# komagoma-2.net
KiCad netlist of a schematic drawn in EAGLE
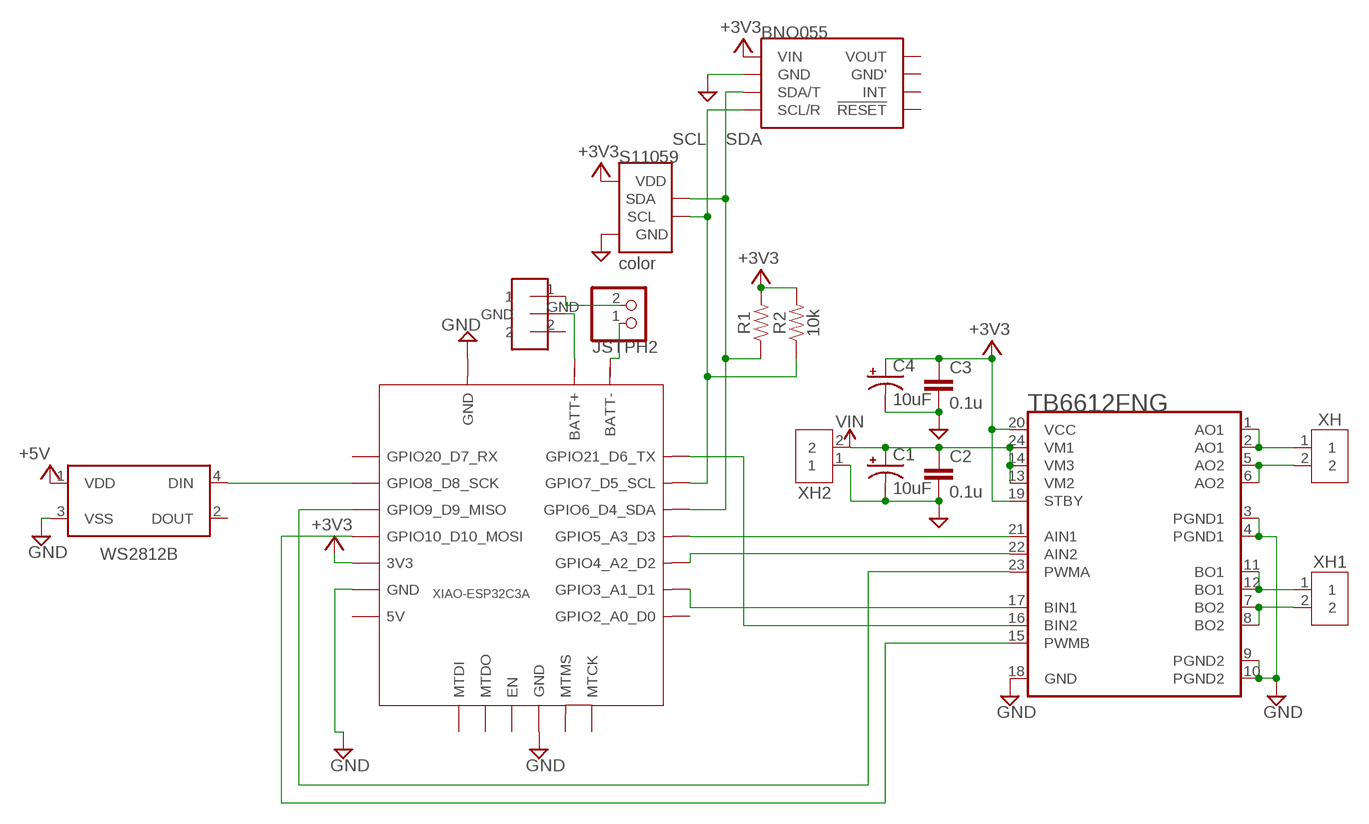
[diagram p0: schematic, sheet 1]

(export (version "E")
  (design (tool "Eeschema 10.0.6"))
  (components
    (comp (ref "C1")
      (value "10uF")
      (footprint "eagle-import:CPOL-RADIAL-2.5MM-5MM-KIT")
      (libsource (lib "eagle-import") (part "10UF-POLAR-RADIAL-2.5MM-KIT-25V-20%"))
    )
    (comp (ref "C2")
      (value "0.1u")
      (footprint "eagle-import:C1608")
      (libsource (lib "eagle-import") (part "C-EUC1608"))
    )
    (comp (ref "C3")
      (value "0.1u")
      (footprint "eagle-import:C1608")
      (libsource (lib "eagle-import") (part "C-EUC1608"))
    )
    (comp (ref "C4")
      (value "10uF")
      (footprint "eagle-import:CPOL-RADIAL-2.5MM-5MM-KIT")
      (libsource (lib "eagle-import") (part "10UF-POLAR-RADIAL-2.5MM-KIT-25V-20%"))
    )
    (comp (ref "CONNECTOR1")
      (value "AKIZUKI_SWITCH_SOCKETAKIZUKI_SWITCH_SOCKET")
      (footprint "eagle-import:AKIZUKI_SWITCH")
      (libsource (lib "eagle-import") (part "AKIZUKI_SWITCH_SOCKETAKIZUKI_SWITCH_SOCKET"))
    )
    (comp (ref "D1")
      (value "WS2812B")
      (footprint "eagle-import:WS2812B")
      (fields (field (name "MANUFACTURER") "Worldsemi"))
      (libsource (lib "eagle-import") (part "WS2812B"))
    )
    (comp (ref "IC1")
      (value "TB6612FNGSSOP24")
      (footprint "eagle-import:SOP65P760X160-24N")
      (fields (field (name "MANUFACTURER") "Toshiba") (field (name "MPN") "TB6612FNG,C,8,EL"))
      (libsource (lib "eagle-import") (part "TB6612FNGSSOP24"))
    )
    (comp (ref "JP1")
      (value "JSTPH2")
      (footprint "eagle-import:JSTPH2")
      (libsource (lib "eagle-import") (part "JSTPH2"))
    )
    (comp (ref "R1")
      (value "10k")
      (footprint "eagle-import:0603")
      (libsource (lib "eagle-import") (part "10KOHM-0603-1/10W-1%"))
    )
    (comp (ref "R2")
      (value "10k")
      (footprint "eagle-import:0603")
      (libsource (lib "eagle-import") (part "10KOHM-0603-1/10W-1%"))
    )
    (comp (ref "U$1")
      (value "BNO055")
      (footprint "eagle-import:BNO055")
      (libsource (lib "eagle-import") (part "BNO055"))
    )
    (comp (ref "U$2")
      (value "S11059")
      (footprint "eagle-import:S11059")
      (libsource (lib "eagle-import") (part "S11059"))
    )
    (comp (ref "U1")
      (value "XIAO-ESP32C3A")
      (footprint "eagle-import:XIAO-ESP32C3-THRUHOLE")
      (libsource (lib "eagle-import") (part "XIAO-ESP32C3A"))
    )
    (comp (ref "XH")
      (value "3A/250V")
      (footprint "eagle-import:B2B-XH-A")
      (fields (field (name "MANUFACTURER") "JST (XH CONNECTOR)") (field (name "MPN") "B2B-XH-A"))
      (libsource (lib "eagle-import") (part "B2B-XH-A"))
    )
    (comp (ref "XH1")
      (value "3A/250V")
      (footprint "eagle-import:B2B-XH-A")
      (fields (field (name "MANUFACTURER") "JST (XH CONNECTOR)") (field (name "MPN") "B2B-XH-A"))
      (libsource (lib "eagle-import") (part "B2B-XH-A"))
    )
    (comp (ref "XH2")
      (value "3A/250V")
      (footprint "eagle-import:B2B-XH-A")
      (fields (field (name "MANUFACTURER") "JST (XH CONNECTOR)") (field (name "MPN") "B2B-XH-A"))
      (libsource (lib "eagle-import") (part "B2B-XH-A"))
    )
  )
  (nets
    (net (code "1") (name "+3V3") (class "Default")
      (node (ref "C3") (pin "1") (pinfunction "1_1") (pintype "passive"))
      (node (ref "C4") (pin "1") (pinfunction "+_1") (pintype "passive"))
      (node (ref "IC1") (pin "19") (pinfunction "STBY_19") (pintype "input"))
      (node (ref "IC1") (pin "20") (pinfunction "VCC_20") (pintype "power_in"))
      (node (ref "R1") (pin "2") (pinfunction "2_2") (pintype "passive"))
      (node (ref "R2") (pin "2") (pinfunction "2_2") (pintype "passive"))
      (node (ref "U$1") (pin "P$1") (pinfunction "VIN_P$1") (pintype "bidirectional"))
      (node (ref "U$2") (pin "P$4") (pinfunction "VDD_P$4") (pintype "bidirectional"))
      (node (ref "U1") (pin "P$12") (pinfunction "3V3_P$12") (pintype "bidirectional"))
    )
    (net (code "2") (name "+5V") (class "Default")
      (node (ref "D1") (pin "1") (pinfunction "VDD_1") (pintype "power_in"))
    )
    (net (code "3") (name "/SCL") (class "Default")
      (node (ref "R2") (pin "1") (pinfunction "1_1") (pintype "passive"))
      (node (ref "U$1") (pin "P$4") (pinfunction "SCL/R_P$4") (pintype "bidirectional"))
      (node (ref "U$2") (pin "P$2") (pinfunction "SCL_P$2") (pintype "bidirectional"))
      (node (ref "U1") (pin "P$6") (pinfunction "GPIO7_D5_SCL_P$6") (pintype "bidirectional"))
    )
    (net (code "4") (name "/SDA") (class "Default")
      (node (ref "R1") (pin "1") (pinfunction "1_1") (pintype "passive"))
      (node (ref "U$1") (pin "P$3") (pinfunction "SDA/T_P$3") (pintype "bidirectional"))
      (node (ref "U$2") (pin "P$3") (pinfunction "SDA_P$3") (pintype "bidirectional"))
      (node (ref "U1") (pin "P$5") (pinfunction "GPIO6_D4_SDA_P$5") (pintype "bidirectional"))
    )
    (net (code "5") (name "GND") (class "Default")
      (node (ref "C1") (pin "2") (pinfunction "-_2") (pintype "passive"))
      (node (ref "C2") (pin "2") (pinfunction "2_2") (pintype "passive"))
      (node (ref "C3") (pin "2") (pinfunction "2_2") (pintype "passive"))
      (node (ref "C4") (pin "2") (pinfunction "-_2") (pintype "passive"))
      (node (ref "D1") (pin "3") (pinfunction "VSS_3") (pintype "power_in"))
      (node (ref "IC1") (pin "10") (pinfunction "PGND2_10") (pintype "power_in"))
      (node (ref "IC1") (pin "18") (pinfunction "GND_18") (pintype "power_in"))
      (node (ref "IC1") (pin "3") (pinfunction "PGND1_3") (pintype "power_in"))
      (node (ref "IC1") (pin "4") (pinfunction "PGND1_4") (pintype "power_in"))
      (node (ref "IC1") (pin "9") (pinfunction "PGND2_9") (pintype "power_in"))
      (node (ref "U$1") (pin "P$2") (pinfunction "GND_P$2") (pintype "bidirectional"))
      (node (ref "U$2") (pin "P$1") (pinfunction "GND_P$1") (pintype "bidirectional"))
      (node (ref "U1") (pin "18") (pinfunction "GND_18") (pintype "bidirectional"))
      (node (ref "U1") (pin "23") (pinfunction "GND_23") (pintype "bidirectional"))
      (node (ref "U1") (pin "P$13") (pinfunction "GND_P$13") (pintype "bidirectional"))
      (node (ref "XH2") (pin "1") (pinfunction "1_1") (pintype "bidirectional"))
    )
    (net (code "6") (name "Net-(C1-+)") (class "Default")
      (node (ref "C1") (pin "1") (pinfunction "+_1") (pintype "passive"))
      (node (ref "C2") (pin "1") (pinfunction "1_1") (pintype "passive"))
      (node (ref "IC1") (pin "13") (pinfunction "VM2_13") (pintype "power_in"))
      (node (ref "IC1") (pin "14") (pinfunction "VM3_14") (pintype "power_in"))
      (node (ref "IC1") (pin "24") (pinfunction "VM1_24") (pintype "power_in"))
      (node (ref "XH2") (pin "2") (pinfunction "2_2") (pintype "bidirectional"))
    )
    (net (code "7") (name "Net-(CONNECTOR1-Pad1)") (class "Default")
      (node (ref "CONNECTOR1") (pin "1") (pinfunction "1_1") (pintype "bidirectional"))
      (node (ref "JP1") (pin "2") (pinfunction "2_2") (pintype "passive"))
    )
    (net (code "8") (name "Net-(D1-DIN)") (class "Default")
      (node (ref "D1") (pin "4") (pinfunction "DIN_4") (pintype "input"))
      (node (ref "U1") (pin "P$9") (pinfunction "GPIO8_D8_SCK_P$9") (pintype "bidirectional"))
    )
    (net (code "9") (name "Net-(IC1-AIN1)") (class "Default")
      (node (ref "IC1") (pin "21") (pinfunction "AIN1_21") (pintype "input"))
      (node (ref "U1") (pin "P$4") (pinfunction "GPIO5_A3_D3_P$4") (pintype "bidirectional"))
    )
    (net (code "10") (name "Net-(IC1-AIN2)") (class "Default")
      (node (ref "IC1") (pin "22") (pinfunction "AIN2_22") (pintype "input"))
      (node (ref "U1") (pin "P$3") (pinfunction "GPIO4_A2_D2_P$3") (pintype "bidirectional"))
    )
    (net (code "11") (name "Net-(IC1-AO1-Pad1)") (class "Default")
      (node (ref "IC1") (pin "1") (pinfunction "AO1_1") (pintype "output"))
      (node (ref "IC1") (pin "2") (pinfunction "AO1_2") (pintype "output"))
      (node (ref "XH") (pin "1") (pinfunction "1_1") (pintype "bidirectional"))
    )
    (net (code "12") (name "Net-(IC1-AO2-Pad5)") (class "Default")
      (node (ref "IC1") (pin "5") (pinfunction "AO2_5") (pintype "output"))
      (node (ref "IC1") (pin "6") (pinfunction "AO2_6") (pintype "output"))
      (node (ref "XH") (pin "2") (pinfunction "2_2") (pintype "bidirectional"))
    )
    (net (code "13") (name "Net-(IC1-BIN1)") (class "Default")
      (node (ref "IC1") (pin "17") (pinfunction "BIN1_17") (pintype "input"))
      (node (ref "U1") (pin "P$2") (pinfunction "GPIO3_A1_D1_P$2") (pintype "bidirectional"))
    )
    (net (code "14") (name "Net-(IC1-BIN2)") (class "Default")
      (node (ref "IC1") (pin "16") (pinfunction "BIN2_16") (pintype "input"))
      (node (ref "U1") (pin "P$7") (pinfunction "GPIO21_D6_TX_P$7") (pintype "bidirectional"))
    )
    (net (code "15") (name "Net-(IC1-BO1-Pad11)") (class "Default")
      (node (ref "IC1") (pin "11") (pinfunction "BO1_11") (pintype "output"))
      (node (ref "IC1") (pin "12") (pinfunction "BO1_12") (pintype "output"))
      (node (ref "XH1") (pin "1") (pinfunction "1_1") (pintype "bidirectional"))
    )
    (net (code "16") (name "Net-(IC1-BO2-Pad7)") (class "Default")
      (node (ref "IC1") (pin "7") (pinfunction "BO2_7") (pintype "output"))
      (node (ref "IC1") (pin "8") (pinfunction "BO2_8") (pintype "output"))
      (node (ref "XH1") (pin "2") (pinfunction "2_2") (pintype "bidirectional"))
    )
    (net (code "17") (name "Net-(IC1-PWMA)") (class "Default")
      (node (ref "IC1") (pin "23") (pinfunction "PWMA_23") (pintype "input"))
      (node (ref "U1") (pin "P$10") (pinfunction "GPIO9_D9_MISO_P$10") (pintype "bidirectional"))
    )
    (net (code "18") (name "Net-(IC1-PWMB)") (class "Default")
      (node (ref "IC1") (pin "15") (pinfunction "PWMB_15") (pintype "input"))
      (node (ref "U1") (pin "P$11") (pinfunction "GPIO10_D10_MOSI_P$11") (pintype "bidirectional"))
    )
    (net (code "19") (name "Net-(U1-BATT+)") (class "Default")
      (node (ref "CONNECTOR1") (pin "GND") (pinfunction "GND_GND") (pintype "bidirectional"))
      (node (ref "U1") (pin "22") (pinfunction "BATT+_22") (pintype "bidirectional"))
    )
    (net (code "20") (name "Net-(U1-BATT-)") (class "Default")
      (node (ref "JP1") (pin "1") (pinfunction "1_1") (pintype "passive"))
      (node (ref "U1") (pin "21") (pinfunction "BATT-_21") (pintype "bidirectional"))
    )
    (net (code "22") (name "unconnected-(CONNECTOR1-Pad2)") (class "Default")
      (node (ref "CONNECTOR1") (pin "2") (pinfunction "2_2") (pintype "bidirectional"))
    )
    (net (code "23") (name "unconnected-(D1-DOUT-Pad2)") (class "Default")
      (node (ref "D1") (pin "2") (pinfunction "DOUT_2") (pintype "output"))
    )
    (net (code "24") (name "unconnected-(U$1-GND'-PadP$7)") (class "Default")
      (node (ref "U$1") (pin "P$7") (pinfunction "GND'_P$7") (pintype "bidirectional"))
    )
    (net (code "25") (name "unconnected-(U$1-INT-PadP$6)") (class "Default")
      (node (ref "U$1") (pin "P$6") (pinfunction "INT_P$6") (pintype "bidirectional"))
    )
    (net (code "26") (name "unconnected-(U$1-VOUT-PadP$8)") (class "Default")
      (node (ref "U$1") (pin "P$8") (pinfunction "VOUT_P$8") (pintype "bidirectional"))
    )
    (net (code "27") (name "unconnected-(U$1-~{RESET}-PadP$5)") (class "Default")
      (node (ref "U$1") (pin "P$5") (pinfunction "~{RESET}_P$5") (pintype "bidirectional"))
    )
    (net (code "28") (name "unconnected-(U1-5V-PadP$14)") (class "Default")
      (node (ref "U1") (pin "P$14") (pinfunction "5V_P$14") (pintype "bidirectional"))
    )
    (net (code "29") (name "unconnected-(U1-EN-Pad17)") (class "Default")
      (node (ref "U1") (pin "17") (pinfunction "EN_17") (pintype "bidirectional"))
    )
    (net (code "30") (name "unconnected-(U1-GPIO2_A0_D0-PadP$1)") (class "Default")
      (node (ref "U1") (pin "P$1") (pinfunction "GPIO2_A0_D0_P$1") (pintype "bidirectional"))
    )
    (net (code "31") (name "unconnected-(U1-GPIO20_D7_RX-PadP$8)") (class "Default")
      (node (ref "U1") (pin "P$8") (pinfunction "GPIO20_D7_RX_P$8") (pintype "bidirectional"))
    )
    (net (code "32") (name "unconnected-(U1-MTCK-Pad20)") (class "Default")
      (node (ref "U1") (pin "20") (pinfunction "MTCK_20") (pintype "bidirectional"))
    )
    (net (code "33") (name "unconnected-(U1-MTDI-Pad15)") (class "Default")
      (node (ref "U1") (pin "15") (pinfunction "MTDI_15") (pintype "bidirectional"))
    )
    (net (code "34") (name "unconnected-(U1-MTDO-Pad16)") (class "Default")
      (node (ref "U1") (pin "16") (pinfunction "MTDO_16") (pintype "bidirectional"))
    )
    (net (code "35") (name "unconnected-(U1-MTMS-Pad19)") (class "Default")
      (node (ref "U1") (pin "19") (pinfunction "MTMS_19") (pintype "bidirectional"))
    )
  )
)
